# LS1.net
KiCad netlist of a schematic drawn in Altium Designer
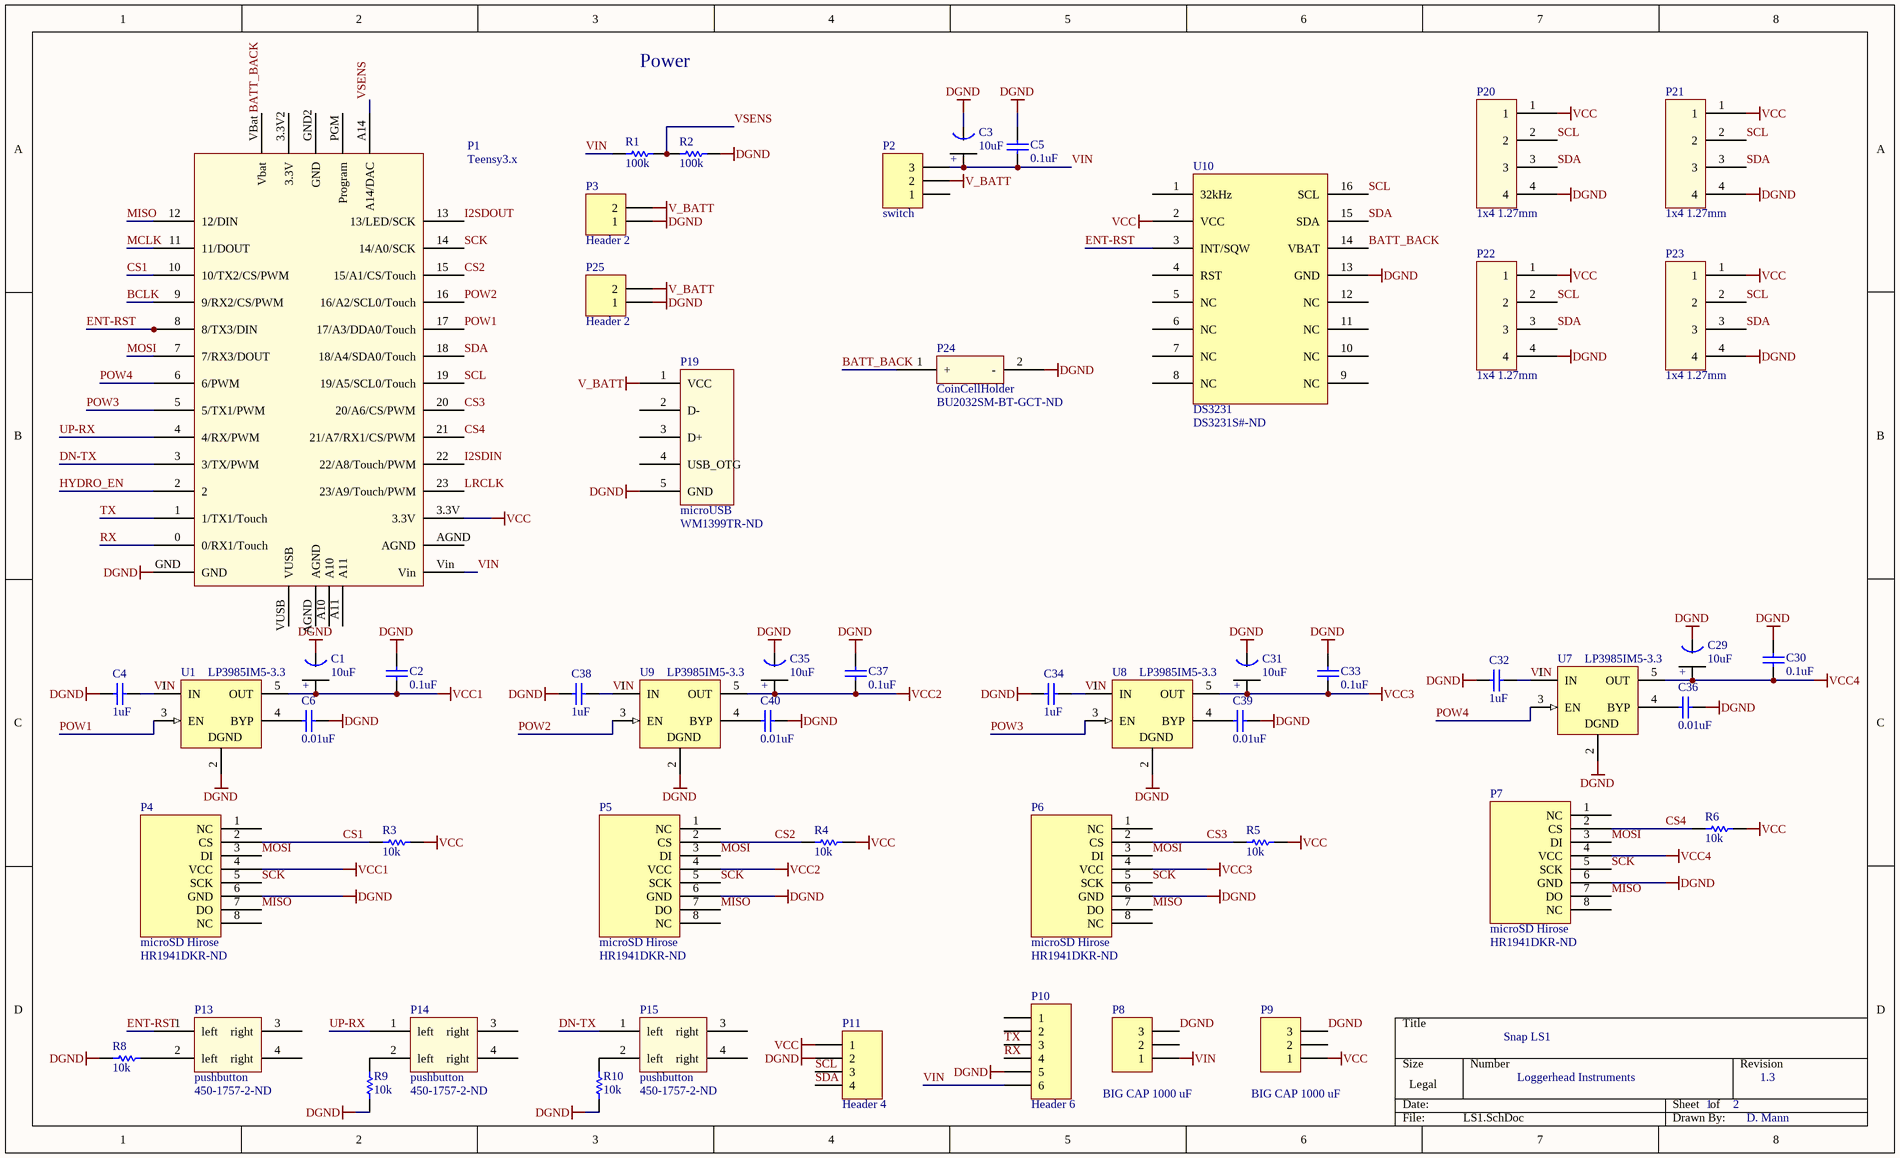
[diagram p0: LS1.SchDoc]

(export (version "E")
  (design (tool "Eeschema 10.0.6"))
  (components
    (comp (ref "C1") (value "10uF") (footprint "Tant0805") (libsource (lib "Loggerhead") (part "Tant0805")))
    (comp (ref "C2")
      (value "0.1uF")
      (footprint "0402")
      (description "Ceramic Chip Capacitor - Standard")
      (fields (field (name "PUBLISHER") "Altium Limited"))
      (libsource (lib "KEMET Chip Capacitor") (part "C0402"))
    )
    (comp (ref "C3") (value "10uF") (footprint "Tant0805") (libsource (lib "Loggerhead") (part "Tant0805")))
    (comp (ref "C4")
      (value "1uF")
      (footprint "0402")
      (description "Ceramic Chip Capacitor - Standard")
      (fields (field (name "PUBLISHER") "Altium Limited"))
      (libsource (lib "KEMET Chip Capacitor") (part "C0402"))
    )
    (comp (ref "C5")
      (value "0.1uF")
      (footprint "0402")
      (description "Ceramic Chip Capacitor - Standard")
      (fields (field (name "PUBLISHER") "Altium Limited"))
      (libsource (lib "KEMET Chip Capacitor") (part "C0402"))
    )
    (comp (ref "C6")
      (value "0.01uF")
      (footprint "0402")
      (description "Ceramic Chip Capacitor - Standard")
      (fields (field (name "PUBLISHER") "Altium Limited"))
      (libsource (lib "KEMET Chip Capacitor") (part "C0402"))
    )
    (comp (ref "C29") (value "10uF") (footprint "Tant0805") (libsource (lib "Loggerhead") (part "Tant0805")))
    (comp (ref "C30")
      (value "0.1uF")
      (footprint "0402")
      (description "Ceramic Chip Capacitor - Standard")
      (fields (field (name "PUBLISHER") "Altium Limited"))
      (libsource (lib "KEMET Chip Capacitor") (part "C0402"))
    )
    (comp (ref "C31") (value "10uF") (footprint "Tant0805") (libsource (lib "Loggerhead") (part "Tant0805")))
    (comp (ref "C32")
      (value "1uF")
      (footprint "0402")
      (description "Ceramic Chip Capacitor - Standard")
      (fields (field (name "PUBLISHER") "Altium Limited"))
      (libsource (lib "KEMET Chip Capacitor") (part "C0402"))
    )
    (comp (ref "C33")
      (value "0.1uF")
      (footprint "0402")
      (description "Ceramic Chip Capacitor - Standard")
      (fields (field (name "PUBLISHER") "Altium Limited"))
      (libsource (lib "KEMET Chip Capacitor") (part "C0402"))
    )
    (comp (ref "C34")
      (value "1uF")
      (footprint "0402")
      (description "Ceramic Chip Capacitor - Standard")
      (fields (field (name "PUBLISHER") "Altium Limited"))
      (libsource (lib "KEMET Chip Capacitor") (part "C0402"))
    )
    (comp (ref "C35") (value "10uF") (footprint "Tant0805") (libsource (lib "Loggerhead") (part "Tant0805")))
    (comp (ref "C36")
      (value "0.01uF")
      (footprint "0402")
      (description "Ceramic Chip Capacitor - Standard")
      (fields (field (name "PUBLISHER") "Altium Limited"))
      (libsource (lib "KEMET Chip Capacitor") (part "C0402"))
    )
    (comp (ref "C37")
      (value "0.1uF")
      (footprint "0402")
      (description "Ceramic Chip Capacitor - Standard")
      (fields (field (name "PUBLISHER") "Altium Limited"))
      (libsource (lib "KEMET Chip Capacitor") (part "C0402"))
    )
    (comp (ref "C38")
      (value "1uF")
      (footprint "0402")
      (description "Ceramic Chip Capacitor - Standard")
      (fields (field (name "PUBLISHER") "Altium Limited"))
      (libsource (lib "KEMET Chip Capacitor") (part "C0402"))
    )
    (comp (ref "C39")
      (value "0.01uF")
      (footprint "0402")
      (description "Ceramic Chip Capacitor - Standard")
      (fields (field (name "PUBLISHER") "Altium Limited"))
      (libsource (lib "KEMET Chip Capacitor") (part "C0402"))
    )
    (comp (ref "C40")
      (value "0.01uF")
      (footprint "0402")
      (description "Ceramic Chip Capacitor - Standard")
      (fields (field (name "PUBLISHER") "Altium Limited"))
      (libsource (lib "KEMET Chip Capacitor") (part "C0402"))
    )
    (comp (ref "P1")
      (value "Teensy3.x")
      (footprint "Teensy3.x")
      (libsource (lib "Teensy") (part "Teensy3.x"))
    )
    (comp (ref "P2")
      (value "switch")
      (footprint "HDR1X3")
      (description "Header, 3-Pin")
      (fields (field (name "PUBLISHER") "Altium Limited"))
      (libsource (lib "Miscellaneous Connectors") (part "Header 3"))
    )
    (comp (ref "P3")
      (value "Header 2")
      (footprint "HDR1X2")
      (description "Header, 2-Pin")
      (fields (field (name "PUBLISHER") "Altium Limited"))
      (libsource (lib "Miscellaneous Connectors") (part "Header 2"))
    )
    (comp (ref "P4")
      (value "microSD Hirose")
      (footprint "DM3D microSD")
      (fields (field (name "SUPPLIER PART NUMBER 1") "HR1941DKR-ND"))
      (libsource (lib "Loggerhead") (part "microSD Hirose"))
    )
    (comp (ref "P5")
      (value "microSD Hirose")
      (footprint "DM3D microSD")
      (fields (field (name "SUPPLIER PART NUMBER 1") "HR1941DKR-ND"))
      (libsource (lib "Loggerhead") (part "microSD Hirose"))
    )
    (comp (ref "P6")
      (value "microSD Hirose")
      (footprint "DM3D microSD")
      (fields (field (name "SUPPLIER PART NUMBER 1") "HR1941DKR-ND"))
      (libsource (lib "Loggerhead") (part "microSD Hirose"))
    )
    (comp (ref "P7")
      (value "microSD Hirose")
      (footprint "DM3D microSD")
      (fields (field (name "SUPPLIER PART NUMBER 1") "HR1941DKR-ND"))
      (libsource (lib "Loggerhead") (part "microSD Hirose"))
    )
    (comp (ref "P8")
      (value "BIG CAP 1000 uF")
      (footprint "HDR1X3")
      (description "Header, 3-Pin")
      (fields (field (name "PUBLISHER") "Altium Limited"))
      (libsource (lib "Miscellaneous Connectors") (part "Header 3"))
    )
    (comp (ref "P9")
      (value "BIG CAP 1000 uF")
      (footprint "HDR1X3")
      (description "Header, 3-Pin")
      (fields (field (name "PUBLISHER") "Altium Limited"))
      (libsource (lib "Miscellaneous Connectors") (part "Header 3"))
    )
    (comp (ref "P10")
      (value "Header 6")
      (footprint "HDR1X6")
      (description "Header, 6-Pin")
      (fields (field (name "PUBLISHER") "Altium Limited"))
      (libsource (lib "Miscellaneous Connectors") (part "Header 6"))
    )
    (comp (ref "P11")
      (value "Header 4")
      (footprint "HDR1X4")
      (description "Header, 4-Pin")
      (fields (field (name "PUBLISHER") "Altium Limited"))
      (libsource (lib "Miscellaneous Connectors") (part "Header 4"))
    )
    (comp (ref "P13")
      (value "pushbutton")
      (footprint "SOP4")
      (fields (field (name "SUPPLIER PART NUMBER 1") "450-1757-2-ND"))
      (libsource (lib "Loggerhead") (part "pushbutton"))
    )
    (comp (ref "P14")
      (value "pushbutton")
      (footprint "SOP4")
      (fields (field (name "SUPPLIER PART NUMBER 1") "450-1757-2-ND"))
      (libsource (lib "Loggerhead") (part "pushbutton"))
    )
    (comp (ref "P15")
      (value "pushbutton")
      (footprint "SOP4")
      (fields (field (name "SUPPLIER PART NUMBER 1") "450-1757-2-ND"))
      (libsource (lib "Loggerhead") (part "pushbutton"))
    )
    (comp (ref "P19")
      (value "microUSB")
      (footprint "microUSB-B")
      (fields (field (name "SUPPLIER PART NUMBER 1") "WM1399TR-ND"))
      (libsource (lib "Loggerhead") (part "microUSB-B"))
    )
    (comp (ref "P20")
      (value "1x4 1.27mm")
      (footprint "Header1x4 1.27mm")
      (libsource (lib "Loggerhead") (part "Header 1x4 1.27mm"))
    )
    (comp (ref "P21")
      (value "1x4 1.27mm")
      (footprint "Header1x4 1.27mm")
      (libsource (lib "Loggerhead") (part "Header 1x4 1.27mm"))
    )
    (comp (ref "P22")
      (value "1x4 1.27mm")
      (footprint "Header1x4 1.27mm")
      (libsource (lib "Loggerhead") (part "Header 1x4 1.27mm"))
    )
    (comp (ref "P23")
      (value "1x4 1.27mm")
      (footprint "Header1x4 1.27mm")
      (libsource (lib "Loggerhead") (part "Header 1x4 1.27mm"))
    )
    (comp (ref "P24")
      (value "CoinCellHolder")
      (footprint "CoinCellHolder")
      (fields (field (name "SUPPLIER PART NUMBER 1") "BU2032SM-BT-GCT-ND"))
      (libsource (lib "Loggerhead") (part "CoinCellHolder"))
    )
    (comp (ref "P25")
      (value "Header 2")
      (footprint "HDR1X2")
      (description "Header, 2-Pin")
      (fields (field (name "PUBLISHER") "Altium Limited"))
      (libsource (lib "Miscellaneous Connectors") (part "Header 2"))
    )
    (comp (ref "R1")
      (value "100k")
      (footprint "3-0603")
      (fields (field (name "PUBLISHER") "Altium Limited"))
      (libsource (lib "Panasonic Resistor") (part "ERJ3RK"))
    )
    (comp (ref "R2")
      (value "100k")
      (footprint "3-0603")
      (fields (field (name "PUBLISHER") "Altium Limited"))
      (libsource (lib "Panasonic Resistor") (part "ERJ3RK"))
    )
    (comp (ref "R3")
      (value "10k")
      (footprint "3-0603")
      (fields (field (name "PUBLISHER") "Altium Limited"))
      (libsource (lib "Panasonic Resistor") (part "ERJ3RK"))
    )
    (comp (ref "R4")
      (value "10k")
      (footprint "3-0603")
      (fields (field (name "PUBLISHER") "Altium Limited"))
      (libsource (lib "Panasonic Resistor") (part "ERJ3RK"))
    )
    (comp (ref "R5")
      (value "10k")
      (footprint "3-0603")
      (fields (field (name "PUBLISHER") "Altium Limited"))
      (libsource (lib "Panasonic Resistor") (part "ERJ3RK"))
    )
    (comp (ref "R6")
      (value "10k")
      (footprint "3-0603")
      (fields (field (name "PUBLISHER") "Altium Limited"))
      (libsource (lib "Panasonic Resistor") (part "ERJ3RK"))
    )
    (comp (ref "R8")
      (value "10k")
      (footprint "3-0603")
      (fields (field (name "PUBLISHER") "Altium Limited"))
      (libsource (lib "Panasonic Resistor") (part "ERJ3RK"))
    )
    (comp (ref "R9")
      (value "10k")
      (footprint "3-0603")
      (fields (field (name "PUBLISHER") "Altium Limited"))
      (libsource (lib "Panasonic Resistor") (part "ERJ3RK"))
    )
    (comp (ref "R10")
      (value "10k")
      (footprint "3-0603")
      (fields (field (name "PUBLISHER") "Altium Limited"))
      (libsource (lib "Panasonic Resistor") (part "ERJ3RK"))
    )
    (comp (ref "U1")
      (value "LP3985IM5-3.3")
      (footprint "MF05A_N")
      (description "Micropower, 150mA Low-Noise Ultra Low-Dropout CMOS Voltage Regulator")
      (fields
        (field (name "MANUFACTURER") "National Semiconductor")
        (field (name "DIGIKEYPARTNUMBER") "LP3985IM5-3.3CT-ND")
        (field (name "PUBLISHER") "Altium Limited")
      )
      (libsource (lib "NSC LDO") (part "LP3985IM5-3.3"))
    )
    (comp (ref "U7")
      (value "LP3985IM5-3.3")
      (footprint "MF05A_N")
      (description "Micropower, 150mA Low-Noise Ultra Low-Dropout CMOS Voltage Regulator")
      (fields
        (field (name "MANUFACTURER") "National Semiconductor")
        (field (name "DIGIKEYPARTNUMBER") "LP3985IM5-3.3CT-ND")
        (field (name "PUBLISHER") "Altium Limited")
      )
      (libsource (lib "NSC LDO") (part "LP3985IM5-3.3"))
    )
    (comp (ref "U8")
      (value "LP3985IM5-3.3")
      (footprint "MF05A_N")
      (description "Micropower, 150mA Low-Noise Ultra Low-Dropout CMOS Voltage Regulator")
      (fields
        (field (name "MANUFACTURER") "National Semiconductor")
        (field (name "DIGIKEYPARTNUMBER") "LP3985IM5-3.3CT-ND")
        (field (name "PUBLISHER") "Altium Limited")
      )
      (libsource (lib "NSC LDO") (part "LP3985IM5-3.3"))
    )
    (comp (ref "U9")
      (value "LP3985IM5-3.3")
      (footprint "MF05A_N")
      (description "Micropower, 150mA Low-Noise Ultra Low-Dropout CMOS Voltage Regulator")
      (fields
        (field (name "MANUFACTURER") "National Semiconductor")
        (field (name "DIGIKEYPARTNUMBER") "LP3985IM5-3.3CT-ND")
        (field (name "PUBLISHER") "Altium Limited")
      )
      (libsource (lib "NSC LDO") (part "LP3985IM5-3.3"))
    )
    (comp (ref "U10")
      (value "DS3231")
      (footprint "DS3231")
      (fields (field (name "SUPPLIER PART NUMBER 1") "DS3231S#-ND"))
      (libsource (lib "Loggerhead") (part "DS3231"))
    )
  )
  (nets
    (net (code "1") (name "/BATT_BACK") (class "Default")
      (node (ref "P1") (pin "VBat") (pinfunction "Vbat_VBat") (pintype "passive"))
      (node (ref "P24") (pin "1") (pinfunction "+_1") (pintype "passive"))
      (node (ref "U10") (pin "14") (pinfunction "VBAT_14") (pintype "power_in"))
    )
    (net (code "2") (name "/BCLK") (class "Default")
      (node (ref "P1") (pin "9") (pinfunction "9/RX2/CS/PWM_9") (pintype "passive"))
    )
    (net (code "3") (name "/CS1") (class "Default")
      (node (ref "P1") (pin "10") (pinfunction "10/TX2/CS/PWM_10") (pintype "passive"))
      (node (ref "P4") (pin "2") (pinfunction "CS_2") (pintype "passive"))
      (node (ref "R3") (pin "2") (pinfunction "2_2") (pintype "passive"))
    )
    (net (code "4") (name "/CS2") (class "Default")
      (node (ref "P1") (pin "15") (pinfunction "15/A1/CS/Touch_15") (pintype "passive"))
      (node (ref "P5") (pin "2") (pinfunction "CS_2") (pintype "passive"))
      (node (ref "R4") (pin "2") (pinfunction "2_2") (pintype "passive"))
    )
    (net (code "5") (name "/CS3") (class "Default")
      (node (ref "P1") (pin "20") (pinfunction "20/A6/CS/PWM_20") (pintype "passive"))
      (node (ref "P6") (pin "2") (pinfunction "CS_2") (pintype "passive"))
      (node (ref "R5") (pin "2") (pinfunction "2_2") (pintype "passive"))
    )
    (net (code "6") (name "/CS4") (class "Default")
      (node (ref "P1") (pin "21") (pinfunction "21/A7/RX1/CS/PWM_21") (pintype "passive"))
      (node (ref "P7") (pin "2") (pinfunction "CS_2") (pintype "passive"))
      (node (ref "R6") (pin "2") (pinfunction "2_2") (pintype "passive"))
    )
    (net (code "7") (name "/DN-TX") (class "Default")
      (node (ref "P1") (pin "3") (pinfunction "3/TX/PWM_3") (pintype "passive"))
      (node (ref "P15") (pin "1") (pinfunction "left_1") (pintype "passive"))
    )
    (net (code "8") (name "/ENT-RST") (class "Default")
      (node (ref "P1") (pin "8") (pinfunction "8/TX3/DIN_8") (pintype "passive"))
      (node (ref "P13") (pin "1") (pinfunction "left_1") (pintype "passive"))
      (node (ref "U10") (pin "3") (pinfunction "INT/SQW_3") (pintype "passive"))
    )
    (net (code "9") (name "/HYDRO_EN") (class "Default")
      (node (ref "P1") (pin "2") (pinfunction "2_2") (pintype "passive"))
    )
    (net (code "10") (name "/I2SDIN") (class "Default")
      (node (ref "P1") (pin "22") (pinfunction "22/A8/Touch/PWM_22") (pintype "passive"))
    )
    (net (code "11") (name "/I2SDOUT") (class "Default")
      (node (ref "P1") (pin "13") (pinfunction "13/LED/SCK_13") (pintype "passive"))
    )
    (net (code "12") (name "/LRCLK") (class "Default")
      (node (ref "P1") (pin "23") (pinfunction "23/A9/Touch/PWM_23") (pintype "passive"))
    )
    (net (code "13") (name "/MCLK") (class "Default")
      (node (ref "P1") (pin "11") (pinfunction "11/DOUT_11") (pintype "passive"))
    )
    (net (code "14") (name "/MISO") (class "Default")
      (node (ref "P1") (pin "12") (pinfunction "12/DIN_12") (pintype "passive"))
      (node (ref "P4") (pin "7") (pinfunction "DO_7") (pintype "passive"))
      (node (ref "P5") (pin "7") (pinfunction "DO_7") (pintype "passive"))
      (node (ref "P6") (pin "7") (pinfunction "DO_7") (pintype "passive"))
      (node (ref "P7") (pin "7") (pinfunction "DO_7") (pintype "passive"))
    )
    (net (code "15") (name "/MOSI") (class "Default")
      (node (ref "P1") (pin "7") (pinfunction "7/RX3/DOUT_7") (pintype "passive"))
      (node (ref "P4") (pin "3") (pinfunction "DI_3") (pintype "passive"))
      (node (ref "P5") (pin "3") (pinfunction "DI_3") (pintype "passive"))
      (node (ref "P6") (pin "3") (pinfunction "DI_3") (pintype "passive"))
      (node (ref "P7") (pin "3") (pinfunction "DI_3") (pintype "passive"))
    )
    (net (code "16") (name "/POW1") (class "Default")
      (node (ref "P1") (pin "17") (pinfunction "17/A3/DDA0/Touch_17") (pintype "passive"))
      (node (ref "U1") (pin "3") (pinfunction "EN_3") (pintype "input"))
    )
    (net (code "17") (name "/POW2") (class "Default")
      (node (ref "P1") (pin "16") (pinfunction "16/A2/SCL0/Touch_16") (pintype "passive"))
      (node (ref "U9") (pin "3") (pinfunction "EN_3") (pintype "input"))
    )
    (net (code "18") (name "/POW3") (class "Default")
      (node (ref "P1") (pin "5") (pinfunction "5/TX1/PWM_5") (pintype "passive"))
      (node (ref "U8") (pin "3") (pinfunction "EN_3") (pintype "input"))
    )
    (net (code "19") (name "/POW4") (class "Default")
      (node (ref "P1") (pin "6") (pinfunction "6/PWM_6") (pintype "passive"))
      (node (ref "U7") (pin "3") (pinfunction "EN_3") (pintype "input"))
    )
    (net (code "20") (name "/RX") (class "Default")
      (node (ref "P1") (pin "0") (pinfunction "0/RX1/Touch_0") (pintype "passive"))
      (node (ref "P10") (pin "4") (pinfunction "4_4") (pintype "passive"))
    )
    (net (code "21") (name "/SCK") (class "Default")
      (node (ref "P1") (pin "14") (pinfunction "14/A0/SCK_14") (pintype "passive"))
      (node (ref "P4") (pin "5") (pinfunction "SCK_5") (pintype "passive"))
      (node (ref "P5") (pin "5") (pinfunction "SCK_5") (pintype "passive"))
      (node (ref "P6") (pin "5") (pinfunction "SCK_5") (pintype "passive"))
      (node (ref "P7") (pin "5") (pinfunction "SCK_5") (pintype "passive"))
    )
    (net (code "22") (name "/SCL") (class "Default")
      (node (ref "P1") (pin "19") (pinfunction "19/A5/SCL0/Touch_19") (pintype "passive"))
      (node (ref "P11") (pin "3") (pinfunction "3_3") (pintype "passive"))
      (node (ref "P20") (pin "2") (pinfunction "2_2") (pintype "passive"))
      (node (ref "P21") (pin "2") (pinfunction "2_2") (pintype "passive"))
      (node (ref "P22") (pin "2") (pinfunction "2_2") (pintype "passive"))
      (node (ref "P23") (pin "2") (pinfunction "2_2") (pintype "passive"))
      (node (ref "U10") (pin "16") (pinfunction "SCL_16") (pintype "passive"))
    )
    (net (code "23") (name "/SDA") (class "Default")
      (node (ref "P1") (pin "18") (pinfunction "18/A4/SDA0/Touch_18") (pintype "passive"))
      (node (ref "P11") (pin "4") (pinfunction "4_4") (pintype "passive"))
      (node (ref "P20") (pin "3") (pinfunction "3_3") (pintype "passive"))
      (node (ref "P21") (pin "3") (pinfunction "3_3") (pintype "passive"))
      (node (ref "P22") (pin "3") (pinfunction "3_3") (pintype "passive"))
      (node (ref "P23") (pin "3") (pinfunction "3_3") (pintype "passive"))
      (node (ref "U10") (pin "15") (pinfunction "SDA_15") (pintype "passive"))
    )
    (net (code "24") (name "/TX") (class "Default")
      (node (ref "P1") (pin "1") (pinfunction "1/TX1/Touch_1") (pintype "passive"))
      (node (ref "P10") (pin "3") (pinfunction "3_3") (pintype "passive"))
    )
    (net (code "25") (name "/UP-RX") (class "Default")
      (node (ref "P1") (pin "4") (pinfunction "4/RX/PWM_4") (pintype "passive"))
      (node (ref "P14") (pin "1") (pinfunction "left_1") (pintype "passive"))
    )
    (net (code "26") (name "/VSENS") (class "Default")
      (node (ref "P1") (pin "A14") (pinfunction "A14/DAC_A14") (pintype "passive"))
      (node (ref "R1") (pin "1") (pinfunction "1_1") (pintype "passive"))
      (node (ref "R2") (pin "2") (pinfunction "2_2") (pintype "passive"))
    )
    (net (code "27") (name "DGND") (class "Default")
      (node (ref "C1") (pin "1") (pinfunction "GND_1") (pintype "passive"))
      (node (ref "C2") (pin "2") (pinfunction "2_2") (pintype "passive"))
      (node (ref "C29") (pin "1") (pinfunction "GND_1") (pintype "passive"))
      (node (ref "C3") (pin "1") (pinfunction "GND_1") (pintype "passive"))
      (node (ref "C30") (pin "2") (pinfunction "2_2") (pintype "passive"))
      (node (ref "C31") (pin "1") (pinfunction "GND_1") (pintype "passive"))
      (node (ref "C32") (pin "2") (pinfunction "2_2") (pintype "passive"))
      (node (ref "C33") (pin "2") (pinfunction "2_2") (pintype "passive"))
      (node (ref "C34") (pin "2") (pinfunction "2_2") (pintype "passive"))
      (node (ref "C35") (pin "1") (pinfunction "GND_1") (pintype "passive"))
      (node (ref "C36") (pin "2") (pinfunction "2_2") (pintype "passive"))
      (node (ref "C37") (pin "2") (pinfunction "2_2") (pintype "passive"))
      (node (ref "C38") (pin "2") (pinfunction "2_2") (pintype "passive"))
      (node (ref "C39") (pin "2") (pinfunction "2_2") (pintype "passive"))
      (node (ref "C4") (pin "2") (pinfunction "2_2") (pintype "passive"))
      (node (ref "C40") (pin "2") (pinfunction "2_2") (pintype "passive"))
      (node (ref "C5") (pin "2") (pinfunction "2_2") (pintype "passive"))
      (node (ref "C6") (pin "2") (pinfunction "2_2") (pintype "passive"))
      (node (ref "P1") (pin "GND") (pinfunction "GND_GND") (pintype "passive"))
      (node (ref "P10") (pin "5") (pinfunction "5_5") (pintype "passive"))
      (node (ref "P11") (pin "2") (pinfunction "2_2") (pintype "passive"))
      (node (ref "P19") (pin "5") (pinfunction "GND_5") (pintype "passive"))
      (node (ref "P20") (pin "4") (pinfunction "4_4") (pintype "passive"))
      (node (ref "P21") (pin "4") (pinfunction "4_4") (pintype "passive"))
      (node (ref "P22") (pin "4") (pinfunction "4_4") (pintype "passive"))
      (node (ref "P23") (pin "4") (pinfunction "4_4") (pintype "passive"))
      (node (ref "P24") (pin "2") (pinfunction "-_2") (pintype "passive"))
      (node (ref "P25") (pin "1") (pinfunction "1_1") (pintype "passive"))
      (node (ref "P3") (pin "1") (pinfunction "1_1") (pintype "passive"))
      (node (ref "P4") (pin "6") (pinfunction "GND_6") (pintype "passive"))
      (node (ref "P5") (pin "6") (pinfunction "GND_6") (pintype "passive"))
      (node (ref "P6") (pin "6") (pinfunction "GND_6") (pintype "passive"))
      (node (ref "P7") (pin "6") (pinfunction "GND_6") (pintype "passive"))
      (node (ref "P8") (pin "3") (pinfunction "3_3") (pintype "passive"))
      (node (ref "P9") (pin "3") (pinfunction "3_3") (pintype "passive"))
      (node (ref "R10") (pin "2") (pinfunction "2_2") (pintype "passive"))
      (node (ref "R2") (pin "1") (pinfunction "1_1") (pintype "passive"))
      (node (ref "R8") (pin "2") (pinfunction "2_2") (pintype "passive"))
      (node (ref "R9") (pin "2") (pinfunction "2_2") (pintype "passive"))
      (node (ref "U1") (pin "2") (pinfunction "GND_2") (pintype "power_in"))
      (node (ref "U10") (pin "13") (pinfunction "GND_13") (pintype "passive"))
      (node (ref "U7") (pin "2") (pinfunction "GND_2") (pintype "power_in"))
      (node (ref "U8") (pin "2") (pinfunction "GND_2") (pintype "power_in"))
      (node (ref "U9") (pin "2") (pinfunction "GND_2") (pintype "power_in"))
    )
    (net (code "28") (name "Net-(P13-left-Pad2)") (class "Default")
      (node (ref "P13") (pin "2") (pinfunction "left_2") (pintype "passive"))
      (node (ref "R8") (pin "1") (pinfunction "1_1") (pintype "passive"))
    )
    (net (code "29") (name "Net-(P14-left-Pad2)") (class "Default")
      (node (ref "P14") (pin "2") (pinfunction "left_2") (pintype "passive"))
      (node (ref "R9") (pin "1") (pinfunction "1_1") (pintype "passive"))
    )
    (net (code "30") (name "Net-(P15-left-Pad2)") (class "Default")
      (node (ref "P15") (pin "2") (pinfunction "left_2") (pintype "passive"))
      (node (ref "R10") (pin "1") (pinfunction "1_1") (pintype "passive"))
    )
    (net (code "31") (name "Net-(U1-BYP)") (class "Default")
      (node (ref "C6") (pin "1") (pinfunction "1_1") (pintype "passive"))
      (node (ref "U1") (pin "4") (pinfunction "BYP_4") (pintype "passive"))
    )
    (net (code "32") (name "Net-(U7-BYP)") (class "Default")
      (node (ref "C36") (pin "1") (pinfunction "1_1") (pintype "passive"))
      (node (ref "U7") (pin "4") (pinfunction "BYP_4") (pintype "passive"))
    )
    (net (code "33") (name "Net-(U8-BYP)") (class "Default")
      (node (ref "C39") (pin "1") (pinfunction "1_1") (pintype "passive"))
      (node (ref "U8") (pin "4") (pinfunction "BYP_4") (pintype "passive"))
    )
    (net (code "34") (name "Net-(U9-BYP)") (class "Default")
      (node (ref "C40") (pin "1") (pinfunction "1_1") (pintype "passive"))
      (node (ref "U9") (pin "4") (pinfunction "BYP_4") (pintype "passive"))
    )
    (net (code "35") (name "VCC") (class "Default")
      (node (ref "P1") (pin "3.3V") (pinfunction "3.3V_3.3V") (pintype "passive"))
      (node (ref "P11") (pin "1") (pinfunction "1_1") (pintype "passive"))
      (node (ref "P20") (pin "1") (pinfunction "1_1") (pintype "passive"))
      (node (ref "P21") (pin "1") (pinfunction "1_1") (pintype "passive"))
      (node (ref "P22") (pin "1") (pinfunction "1_1") (pintype "passive"))
      (node (ref "P23") (pin "1") (pinfunction "1_1") (pintype "passive"))
      (node (ref "P9") (pin "1") (pinfunction "1_1") (pintype "passive"))
      (node (ref "R3") (pin "1") (pinfunction "1_1") (pintype "passive"))
      (node (ref "R4") (pin "1") (pinfunction "1_1") (pintype "passive"))
      (node (ref "R5") (pin "1") (pinfunction "1_1") (pintype "passive"))
      (node (ref "R6") (pin "1") (pinfunction "1_1") (pintype "passive"))
      (node (ref "U10") (pin "2") (pinfunction "VCC_2") (pintype "power_in"))
    )
    (net (code "36") (name "VCC1") (class "Default")
      (node (ref "C1") (pin "2") (pinfunction "+_2") (pintype "passive"))
      (node (ref "C2") (pin "1") (pinfunction "1_1") (pintype "passive"))
      (node (ref "P4") (pin "4") (pinfunction "VCC_4") (pintype "passive"))
      (node (ref "U1") (pin "5") (pinfunction "OUT_5") (pintype "power_in"))
    )
    (net (code "37") (name "VCC2") (class "Default")
      (node (ref "C35") (pin "2") (pinfunction "+_2") (pintype "passive"))
      (node (ref "C37") (pin "1") (pinfunction "1_1") (pintype "passive"))
      (node (ref "P5") (pin "4") (pinfunction "VCC_4") (pintype "passive"))
      (node (ref "U9") (pin "5") (pinfunction "OUT_5") (pintype "power_in"))
    )
    (net (code "38") (name "VCC3") (class "Default")
      (node (ref "C31") (pin "2") (pinfunction "+_2") (pintype "passive"))
      (node (ref "C33") (pin "1") (pinfunction "1_1") (pintype "passive"))
      (node (ref "P6") (pin "4") (pinfunction "VCC_4") (pintype "passive"))
      (node (ref "U8") (pin "5") (pinfunction "OUT_5") (pintype "power_in"))
    )
    (net (code "39") (name "VCC4") (class "Default")
      (node (ref "C29") (pin "2") (pinfunction "+_2") (pintype "passive"))
      (node (ref "C30") (pin "1") (pinfunction "1_1") (pintype "passive"))
      (node (ref "P7") (pin "4") (pinfunction "VCC_4") (pintype "passive"))
      (node (ref "U7") (pin "5") (pinfunction "OUT_5") (pintype "power_in"))
    )
    (net (code "40") (name "VIN") (class "Default")
      (node (ref "C3") (pin "2") (pinfunction "+_2") (pintype "passive"))
      (node (ref "C32") (pin "1") (pinfunction "1_1") (pintype "passive"))
      (node (ref "C34") (pin "1") (pinfunction "1_1") (pintype "passive"))
      (node (ref "C38") (pin "1") (pinfunction "1_1") (pintype "passive"))
      (node (ref "C4") (pin "1") (pinfunction "1_1") (pintype "passive"))
      (node (ref "C5") (pin "1") (pinfunction "1_1") (pintype "passive"))
      (node (ref "P1") (pin "Vin") (pinfunction "Vin_Vin") (pintype "passive"))
      (node (ref "P10") (pin "6") (pinfunction "6_6") (pintype "passive"))
      (node (ref "P2") (pin "3") (pinfunction "3_3") (pintype "passive"))
      (node (ref "P8") (pin "1") (pinfunction "1_1") (pintype "passive"))
      (node (ref "R1") (pin "2") (pinfunction "2_2") (pintype "passive"))
      (node (ref "U1") (pin "1") (pinfunction "IN_1") (pintype "power_in"))
      (node (ref "U7") (pin "1") (pinfunction "IN_1") (pintype "power_in"))
      (node (ref "U8") (pin "1") (pinfunction "IN_1") (pintype "power_in"))
      (node (ref "U9") (pin "1") (pinfunction "IN_1") (pintype "power_in"))
    )
    (net (code "41") (name "V_BATT") (class "Default")
      (node (ref "P19") (pin "1") (pinfunction "VCC_1") (pintype "passive"))
      (node (ref "P2") (pin "2") (pinfunction "2_2") (pintype "passive"))
      (node (ref "P25") (pin "2") (pinfunction "2_2") (pintype "passive"))
      (node (ref "P3") (pin "2") (pinfunction "2_2") (pintype "passive"))
    )
    (net (code "42") (name "unconnected-(P1-3.3V-Pad3.3V2)") (class "Default")
      (node (ref "P1") (pin "3.3V2") (pinfunction "3.3V_3.3V2") (pintype "passive"))
    )
    (net (code "43") (name "unconnected-(P1-GND-PadGND2)") (class "Default")
      (node (ref "P1") (pin "GND2") (pinfunction "GND_GND2") (pintype "passive"))
    )
    (net (code "44") (name "unconnected-(P1-PadA10)") (class "Default")
      (node (ref "P1") (pin "A10") (pinfunction "A10_A10") (pintype "passive"))
    )
    (net (code "45") (name "unconnected-(P1-PadA11)") (class "Default")
      (node (ref "P1") (pin "A11") (pinfunction "A11_A11") (pintype "passive"))
    )
    (net (code "46") (name "unconnected-(P1-PadAGND)") (class "Default")
      (node (ref "P1") (pin "AGND") (pinfunction "AGND_AGND") (pintype "passive"))
    )
    (net (code "47") (name "unconnected-(P1-PadAGND)_1") (class "Default")
      (node (ref "P1") (pin "AGND") (pinfunction "AGND_AGND") (pintype "passive"))
    )
    (net (code "48") (name "unconnected-(P1-PadVUSB)") (class "Default")
      (node (ref "P1") (pin "VUSB") (pinfunction "VUSB_VUSB") (pintype "passive"))
    )
    (net (code "49") (name "unconnected-(P1-Program-PadPGM)") (class "Default")
      (node (ref "P1") (pin "PGM") (pinfunction "Program_PGM") (pintype "passive"))
    )
    (net (code "50") (name "unconnected-(P2-Pad1)") (class "Default")
      (node (ref "P2") (pin "1") (pinfunction "1_1") (pintype "passive"))
    )
    (net (code "51") (name "unconnected-(P4-NC-Pad1)") (class "Default")
      (node (ref "P4") (pin "1") (pinfunction "NC_1") (pintype "passive"))
    )
    (net (code "52") (name "unconnected-(P4-NC-Pad8)") (class "Default")
      (node (ref "P4") (pin "8") (pinfunction "NC_8") (pintype "passive"))
    )
    (net (code "53") (name "unconnected-(P5-NC-Pad1)") (class "Default")
      (node (ref "P5") (pin "1") (pinfunction "NC_1") (pintype "passive"))
    )
    (net (code "54") (name "unconnected-(P5-NC-Pad8)") (class "Default")
      (node (ref "P5") (pin "8") (pinfunction "NC_8") (pintype "passive"))
    )
    (net (code "55") (name "unconnected-(P6-NC-Pad1)") (class "Default")
      (node (ref "P6") (pin "1") (pinfunction "NC_1") (pintype "passive"))
    )
    (net (code "56") (name "unconnected-(P6-NC-Pad8)") (class "Default")
      (node (ref "P6") (pin "8") (pinfunction "NC_8") (pintype "passive"))
    )
    (net (code "57") (name "unconnected-(P7-NC-Pad1)") (class "Default")
      (node (ref "P7") (pin "1") (pinfunction "NC_1") (pintype "passive"))
    )
    (net (code "58") (name "unconnected-(P7-NC-Pad8)") (class "Default")
      (node (ref "P7") (pin "8") (pinfunction "NC_8") (pintype "passive"))
    )
    (net (code "59") (name "unconnected-(P8-Pad2)") (class "Default")
      (node (ref "P8") (pin "2") (pinfunction "2_2") (pintype "passive"))
    )
    (net (code "60") (name "unconnected-(P9-Pad2)") (class "Default")
      (node (ref "P9") (pin "2") (pinfunction "2_2") (pintype "passive"))
    )
    (net (code "61") (name "unconnected-(P10-Pad1)") (class "Default")
      (node (ref "P10") (pin "1") (pinfunction "1_1") (pintype "passive"))
    )
    (net (code "62") (name "unconnected-(P10-Pad2)") (class "Default")
      (node (ref "P10") (pin "2") (pinfunction "2_2") (pintype "passive"))
    )
    (net (code "63") (name "unconnected-(P13-right-Pad3)") (class "Default")
      (node (ref "P13") (pin "3") (pinfunction "right_3") (pintype "passive"))
    )
    (net (code "64") (name "unconnected-(P13-right-Pad4)") (class "Default")
      (node (ref "P13") (pin "4") (pinfunction "right_4") (pintype "passive"))
    )
    (net (code "65") (name "unconnected-(P14-right-Pad3)") (class "Default")
      (node (ref "P14") (pin "3") (pinfunction "right_3") (pintype "passive"))
    )
    (net (code "66") (name "unconnected-(P14-right-Pad4)") (class "Default")
      (node (ref "P14") (pin "4") (pinfunction "right_4") (pintype "passive"))
    )
    (net (code "67") (name "unconnected-(P15-right-Pad3)") (class "Default")
      (node (ref "P15") (pin "3") (pinfunction "right_3") (pintype "passive"))
    )
    (net (code "68") (name "unconnected-(P15-right-Pad4)") (class "Default")
      (node (ref "P15") (pin "4") (pinfunction "right_4") (pintype "passive"))
    )
    (net (code "69") (name "unconnected-(P19-D+-Pad3)") (class "Default")
      (node (ref "P19") (pin "3") (pinfunction "D+_3") (pintype "passive"))
    )
    (net (code "70") (name "unconnected-(P19-D--Pad2)") (class "Default")
      (node (ref "P19") (pin "2") (pinfunction "D-_2") (pintype "passive"))
    )
    (net (code "71") (name "unconnected-(P19-USB_OTG-Pad4)") (class "Default")
      (node (ref "P19") (pin "4") (pinfunction "USB_OTG_4") (pintype "passive"))
    )
    (net (code "72") (name "unconnected-(U10-32kHz-Pad1)") (class "Default")
      (node (ref "U10") (pin "1") (pinfunction "32kHz_1") (pintype "passive"))
    )
    (net (code "73") (name "unconnected-(U10-NC-Pad5)") (class "Default")
      (node (ref "U10") (pin "5") (pinfunction "NC_5") (pintype "passive"))
    )
    (net (code "74") (name "unconnected-(U10-NC-Pad6)") (class "Default")
      (node (ref "U10") (pin "6") (pinfunction "NC_6") (pintype "passive"))
    )
    (net (code "75") (name "unconnected-(U10-NC-Pad7)") (class "Default")
      (node (ref "U10") (pin "7") (pinfunction "NC_7") (pintype "passive"))
    )
    (net (code "76") (name "unconnected-(U10-NC-Pad8)") (class "Default")
      (node (ref "U10") (pin "8") (pinfunction "NC_8") (pintype "passive"))
    )
    (net (code "77") (name "unconnected-(U10-NC-Pad9)") (class "Default")
      (node (ref "U10") (pin "9") (pinfunction "NC_9") (pintype "passive"))
    )
    (net (code "78") (name "unconnected-(U10-NC-Pad10)") (class "Default")
      (node (ref "U10") (pin "10") (pinfunction "NC_10") (pintype "passive"))
    )
    (net (code "79") (name "unconnected-(U10-NC-Pad11)") (class "Default")
      (node (ref "U10") (pin "11") (pinfunction "NC_11") (pintype "passive"))
    )
    (net (code "80") (name "unconnected-(U10-NC-Pad12)") (class "Default")
      (node (ref "U10") (pin "12") (pinfunction "NC_12") (pintype "passive"))
    )
    (net (code "81") (name "unconnected-(U10-RST-Pad4)") (class "Default")
      (node (ref "U10") (pin "4") (pinfunction "RST_4") (pintype "passive"))
    )
  )
)
